# EPS_Distribution_LCL-TK.net
KiCad netlist of a schematic drawn in Altium Designer
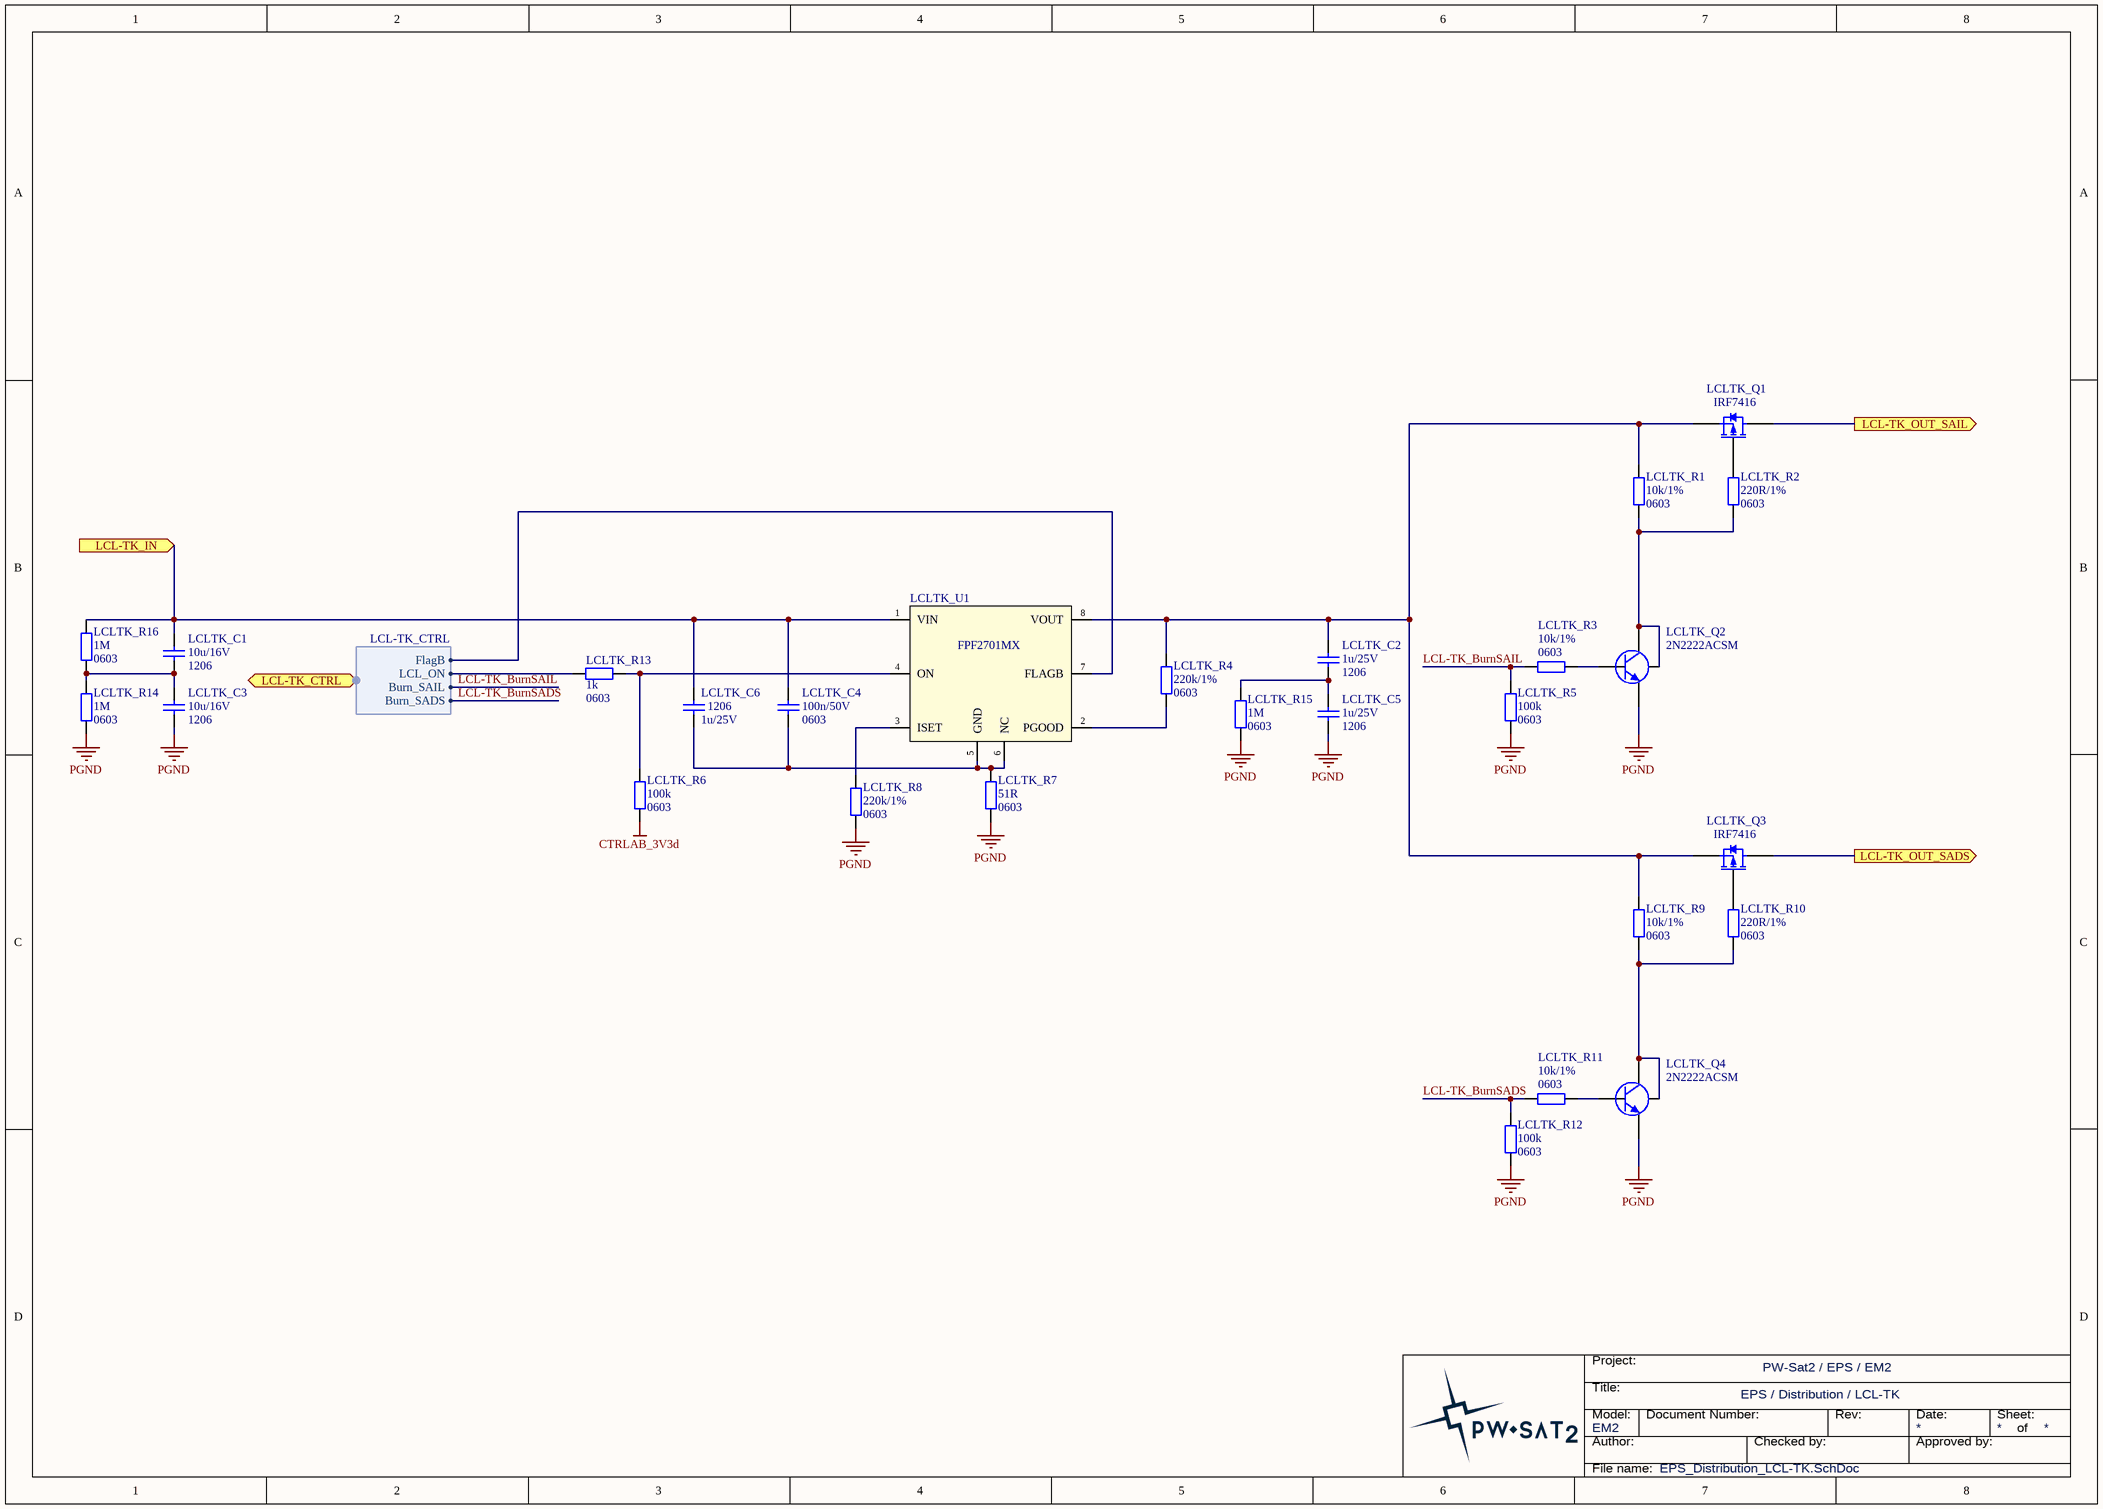
[diagram p0: EPS_Distribution_LCL-TK.SchDoc]

(export (version "E")
  (design (tool "Eeschema 10.0.6"))
  (components
    (comp (ref "LCLTK_C1")
      (value "10u/16V")
      (footprint "SMD_Capacitor_1206")
      (description "Ceramic Cap Kemet COTS 10u/16V X7R 1206")
      (fields
        (field (name "MANUFACTURERPARTNUMBER") "C1206T106K4RACTU")
        (field (name "MANUFACTURER") "Kemet")
        (field (name "PACKGE") "1206")
      )
      (libsource (lib "capacitors") (part "Cer_C1206T106K4RACTU"))
    )
    (comp (ref "LCLTK_C2")
      (value "1u/25V")
      (footprint "SMD_Capacitor_1206")
      (description "Ceramic Cap Kemet COTS 1u/25V X7R 1206")
      (fields
        (field (name "MANUFACTURERPARTNUMBER") "C1206T105K3RALTU")
        (field (name "MANUFACTURER") "Kemet")
        (field (name "PACKAGE") "1206")
      )
      (libsource (lib "capacitors") (part "Cer_C1206T105K3RALTU"))
    )
    (comp (ref "LCLTK_C3")
      (value "10u/16V")
      (footprint "SMD_Capacitor_1206")
      (description "Ceramic Cap Kemet COTS 10u/16V X7R 1206")
      (fields
        (field (name "MANUFACTURERPARTNUMBER") "C1206T106K4RACTU")
        (field (name "MANUFACTURER") "Kemet")
        (field (name "PACKGE") "1206")
      )
      (libsource (lib "capacitors") (part "Cer_C1206T106K4RACTU"))
    )
    (comp (ref "LCLTK_C4")
      (value "100n/50V")
      (footprint "SMD_Capacitor_0603")
      (description "Ceramic Cap Kemet COTS 100n/50V X7R 0603")
      (fields
        (field (name "MANUFACTURER") "Kemet")
        (field (name "MANUFACTURERPARTNUMBER") "C0603T104K5RALTU")
        (field (name "PACKAGE") "0603")
      )
      (libsource (lib "capacitors") (part "Cer_C0603T104K5RALTU"))
    )
    (comp (ref "LCLTK_C5")
      (value "1u/25V")
      (footprint "SMD_Capacitor_1206")
      (description "Ceramic Cap Kemet COTS 1u/25V X7R 1206")
      (fields
        (field (name "MANUFACTURERPARTNUMBER") "C1206T105K3RALTU")
        (field (name "MANUFACTURER") "Kemet")
        (field (name "PACKAGE") "1206")
      )
      (libsource (lib "capacitors") (part "Cer_C1206T105K3RALTU"))
    )
    (comp (ref "LCLTK_C6")
      (value "1u/25V")
      (footprint "SMD_Capacitor_1206")
      (description "Ceramic Cap Kemet COTS 1u/25V X7R 1206")
      (fields
        (field (name "MANUFACTURERPARTNUMBER") "C1206T105K3RALTU")
        (field (name "MANUFACTURER") "Kemet")
        (field (name "PACKAGE") "1206")
      )
      (libsource (lib "capacitors") (part "Cer_C1206T105K3RALTU"))
    )
    (comp (ref "LCLTK_Q1")
      (value "IRF7416")
      (footprint "SOIC-8-N_SSSGDDDD")
      (description "10A/30V HEXFET Power P-MOSFET.")
      (fields (field (name "MANUFACTURER") "International Rectifier"))
      (libsource (lib "transistors") (part "IRF7416"))
    )
    (comp (ref "LCLTK_Q2")
      (value "2N2222ACSM")
      (footprint "LCC1-4_BEC")
      (description "Silicon Planar Epitaxial NPN Transistor.")
      (fields (field (name "MANUFACTURER") "Semelab-TT"))
      (libsource (lib "transistors") (part "2N2222ACSM"))
    )
    (comp (ref "LCLTK_Q3")
      (value "IRF7416")
      (footprint "SOIC-8-N_SSSGDDDD")
      (description "10A/30V HEXFET Power P-MOSFET.")
      (fields (field (name "MANUFACTURER") "International Rectifier"))
      (libsource (lib "transistors") (part "IRF7416"))
    )
    (comp (ref "LCLTK_Q4")
      (value "2N2222ACSM")
      (footprint "LCC1-4_BEC")
      (description "Silicon Planar Epitaxial NPN Transistor.")
      (fields (field (name "MANUFACTURER") "Semelab-TT"))
      (libsource (lib "transistors") (part "2N2222ACSM"))
    )
    (comp (ref "LCLTK_R1")
      (value "10k/1%")
      (footprint "SMD_Resistor_0603")
      (fields (field (name "PACKAGE") "0603"))
      (libsource (lib "resistors") (part "Res"))
    )
    (comp (ref "LCLTK_R2")
      (value "220R/1%")
      (footprint "SMD_Resistor_0603")
      (fields (field (name "PACKAGE") "0603"))
      (libsource (lib "resistors") (part "Res"))
    )
    (comp (ref "LCLTK_R3")
      (value "10k/1%")
      (footprint "SMD_Resistor_0603")
      (fields (field (name "PACKAGE") "0603"))
      (libsource (lib "") (part "Res_1"))
    )
    (comp (ref "LCLTK_R4")
      (value "220k/1%")
      (footprint "SMD_Resistor_0603")
      (fields (field (name "PACKAGE") "0603"))
      (libsource (lib "resistors") (part "Res"))
    )
    (comp (ref "LCLTK_R5")
      (value "100k")
      (footprint "SMD_Resistor_0603")
      (fields (field (name "PACKAGE") "0603"))
      (libsource (lib "resistors") (part "Res"))
    )
    (comp (ref "LCLTK_R6")
      (value "100k")
      (footprint "SMD_Resistor_0603")
      (fields (field (name "PACKAGE") "0603"))
      (libsource (lib "resistors") (part "Res"))
    )
    (comp (ref "LCLTK_R7")
      (value "51R")
      (footprint "SMD_Resistor_0603")
      (fields (field (name "PACKAGE") "0603"))
      (libsource (lib "resistors") (part "Res"))
    )
    (comp (ref "LCLTK_R8")
      (value "220k/1%")
      (footprint "SMD_Resistor_0603")
      (fields (field (name "PACKAGE") "0603"))
      (libsource (lib "resistors") (part "Res"))
    )
    (comp (ref "LCLTK_R9")
      (value "10k/1%")
      (footprint "SMD_Resistor_0603")
      (fields (field (name "PACKAGE") "0603"))
      (libsource (lib "resistors") (part "Res"))
    )
    (comp (ref "LCLTK_R10")
      (value "220R/1%")
      (footprint "SMD_Resistor_0603")
      (fields (field (name "PACKAGE") "0603"))
      (libsource (lib "resistors") (part "Res"))
    )
    (comp (ref "LCLTK_R11")
      (value "10k/1%")
      (footprint "SMD_Resistor_0603")
      (fields (field (name "PACKAGE") "0603"))
      (libsource (lib "") (part "Res_1"))
    )
    (comp (ref "LCLTK_R12")
      (value "100k")
      (footprint "SMD_Resistor_0603")
      (fields (field (name "PACKAGE") "0603"))
      (libsource (lib "resistors") (part "Res"))
    )
    (comp (ref "LCLTK_R13")
      (value "1k")
      (footprint "SMD_Resistor_0603")
      (fields (field (name "PACKAGE") "0603"))
      (libsource (lib "") (part "Res_1"))
    )
    (comp (ref "LCLTK_R14")
      (value "1M")
      (footprint "SMD_Resistor_0603")
      (fields (field (name "PACKAGE") "0603"))
      (libsource (lib "resistors") (part "Res"))
    )
    (comp (ref "LCLTK_R15")
      (value "1M")
      (footprint "SMD_Resistor_0603")
      (fields (field (name "PACKAGE") "0603"))
      (libsource (lib "resistors") (part "Res"))
    )
    (comp (ref "LCLTK_R16")
      (value "1M")
      (footprint "SMD_Resistor_0603")
      (fields (field (name "PACKAGE") "0603"))
      (libsource (lib "resistors") (part "Res"))
    )
    (comp (ref "LCLTK_U1")
      (value "FPF2701MX")
      (footprint "SOIC-8-N")
      (description "Adj over-current protection 0.4-2A, Load Switch")
      (fields (field (name "MANUFACTURER") "Fairchild Semiconductor"))
      (libsource (lib "microcircuits") (part "FPF2701MX"))
    )
  )
  (nets
    (net (code "2") (name "/FlagB") (class "Default")
      (node (ref "LCLTK_U1") (pin "7") (pinfunction "FLAGB_7") (pintype "passive"))
    )
    (net (code "3") (name "/LCL-TK_BurnSADS") (class "Default")
      (node (ref "LCLTK_R11") (pin "2") (pinfunction "2_2") (pintype "passive"))
      (node (ref "LCLTK_R12") (pin "2") (pinfunction "2_2") (pintype "passive"))
    )
    (net (code "4") (name "/LCL-TK_BurnSAIL") (class "Default")
      (node (ref "LCLTK_R3") (pin "2") (pinfunction "2_2") (pintype "passive"))
      (node (ref "LCLTK_R5") (pin "2") (pinfunction "2_2") (pintype "passive"))
    )
    (net (code "5") (name "/LCL-TK_IN") (class "Default")
      (node (ref "LCLTK_C1") (pin "1") (pinfunction "1_1") (pintype "passive"))
      (node (ref "LCLTK_C4") (pin "1") (pinfunction "1_1") (pintype "passive"))
      (node (ref "LCLTK_C6") (pin "1") (pinfunction "1_1") (pintype "passive"))
      (node (ref "LCLTK_R16") (pin "2") (pinfunction "2_2") (pintype "passive"))
      (node (ref "LCLTK_U1") (pin "1") (pinfunction "VIN_1") (pintype "passive"))
    )
    (net (code "6") (name "/LCL-TK_OUT_SADS") (class "Default")
      (node (ref "LCLTK_Q3") (pin "D") (pinfunction "D_D") (pintype "passive"))
    )
    (net (code "7") (name "/LCL-TK_OUT_SAIL") (class "Default")
      (node (ref "LCLTK_Q1") (pin "D") (pinfunction "D_D") (pintype "passive"))
    )
    (net (code "8") (name "/LCL_ON") (class "Default")
      (node (ref "LCLTK_R13") (pin "2") (pinfunction "2_2") (pintype "passive"))
    )
    (net (code "10") (name "CTRLAB_3V3d") (class "Default")
      (node (ref "LCLTK_R6") (pin "1") (pinfunction "1_1") (pintype "passive"))
    )
    (net (code "11") (name "Net-(LCLTK_C1-Pad2)") (class "Default")
      (node (ref "LCLTK_C1") (pin "2") (pinfunction "2_2") (pintype "passive"))
      (node (ref "LCLTK_C3") (pin "1") (pinfunction "1_1") (pintype "passive"))
      (node (ref "LCLTK_R14") (pin "2") (pinfunction "2_2") (pintype "passive"))
      (node (ref "LCLTK_R16") (pin "1") (pinfunction "1_1") (pintype "passive"))
    )
    (net (code "12") (name "Net-(LCLTK_C2-Pad2)") (class "Default")
      (node (ref "LCLTK_C2") (pin "2") (pinfunction "2_2") (pintype "passive"))
      (node (ref "LCLTK_C5") (pin "1") (pinfunction "1_1") (pintype "passive"))
      (node (ref "LCLTK_R15") (pin "2") (pinfunction "2_2") (pintype "passive"))
    )
    (net (code "13") (name "Net-(LCLTK_Q1-PadG)") (class "Default")
      (node (ref "LCLTK_Q1") (pin "G") (pinfunction "G_G") (pintype "passive"))
      (node (ref "LCLTK_R2") (pin "2") (pinfunction "2_2") (pintype "passive"))
    )
    (net (code "14") (name "Net-(LCLTK_Q2-PadB)") (class "Default")
      (node (ref "LCLTK_Q2") (pin "B") (pinfunction "B_B") (pintype "passive"))
      (node (ref "LCLTK_R3") (pin "1") (pinfunction "1_1") (pintype "passive"))
    )
    (net (code "15") (name "Net-(LCLTK_Q2-PadC)") (class "Default")
      (node (ref "LCLTK_Q2") (pin "C") (pinfunction "C_C") (pintype "passive"))
      (node (ref "LCLTK_Q2") (pin "Shield") (pinfunction "Shield_Shield") (pintype "passive"))
      (node (ref "LCLTK_R1") (pin "1") (pinfunction "1_1") (pintype "passive"))
      (node (ref "LCLTK_R2") (pin "1") (pinfunction "1_1") (pintype "passive"))
    )
    (net (code "16") (name "Net-(LCLTK_Q3-PadG)") (class "Default")
      (node (ref "LCLTK_Q3") (pin "G") (pinfunction "G_G") (pintype "passive"))
      (node (ref "LCLTK_R10") (pin "2") (pinfunction "2_2") (pintype "passive"))
    )
    (net (code "17") (name "Net-(LCLTK_Q4-PadB)") (class "Default")
      (node (ref "LCLTK_Q4") (pin "B") (pinfunction "B_B") (pintype "passive"))
      (node (ref "LCLTK_R11") (pin "1") (pinfunction "1_1") (pintype "passive"))
    )
    (net (code "18") (name "Net-(LCLTK_Q4-PadC)") (class "Default")
      (node (ref "LCLTK_Q4") (pin "C") (pinfunction "C_C") (pintype "passive"))
      (node (ref "LCLTK_Q4") (pin "Shield") (pinfunction "Shield_Shield") (pintype "passive"))
      (node (ref "LCLTK_R10") (pin "1") (pinfunction "1_1") (pintype "passive"))
      (node (ref "LCLTK_R9") (pin "1") (pinfunction "1_1") (pintype "passive"))
    )
    (net (code "19") (name "Net-(LCLTK_U1-GND)") (class "Default")
      (node (ref "LCLTK_C4") (pin "2") (pinfunction "2_2") (pintype "passive"))
      (node (ref "LCLTK_C6") (pin "2") (pinfunction "2_2") (pintype "passive"))
      (node (ref "LCLTK_R7") (pin "2") (pinfunction "2_2") (pintype "passive"))
      (node (ref "LCLTK_U1") (pin "5") (pinfunction "GND_5") (pintype "passive"))
      (node (ref "LCLTK_U1") (pin "6") (pinfunction "NC_6") (pintype "passive"))
    )
    (net (code "20") (name "Net-(LCLTK_U1-ISET)") (class "Default")
      (node (ref "LCLTK_R8") (pin "2") (pinfunction "2_2") (pintype "passive"))
      (node (ref "LCLTK_U1") (pin "3") (pinfunction "ISET_3") (pintype "passive"))
    )
    (net (code "21") (name "Net-(LCLTK_U1-ON)") (class "Default")
      (node (ref "LCLTK_R13") (pin "1") (pinfunction "1_1") (pintype "passive"))
      (node (ref "LCLTK_R6") (pin "2") (pinfunction "2_2") (pintype "passive"))
      (node (ref "LCLTK_U1") (pin "4") (pinfunction "ON_4") (pintype "passive"))
    )
    (net (code "22") (name "Net-(LCLTK_U1-PGOOD)") (class "Default")
      (node (ref "LCLTK_R4") (pin "1") (pinfunction "1_1") (pintype "passive"))
      (node (ref "LCLTK_U1") (pin "2") (pinfunction "PGOOD_2") (pintype "passive"))
    )
    (net (code "23") (name "Net-(LCLTK_U1-VOUT)") (class "Default")
      (node (ref "LCLTK_C2") (pin "1") (pinfunction "1_1") (pintype "passive"))
      (node (ref "LCLTK_Q1") (pin "S") (pinfunction "S_S") (pintype "passive"))
      (node (ref "LCLTK_Q3") (pin "S") (pinfunction "S_S") (pintype "passive"))
      (node (ref "LCLTK_R1") (pin "2") (pinfunction "2_2") (pintype "passive"))
      (node (ref "LCLTK_R4") (pin "2") (pinfunction "2_2") (pintype "passive"))
      (node (ref "LCLTK_R9") (pin "2") (pinfunction "2_2") (pintype "passive"))
      (node (ref "LCLTK_U1") (pin "8") (pinfunction "VOUT_8") (pintype "passive"))
    )
    (net (code "24") (name "PGND") (class "Default")
      (node (ref "LCLTK_C3") (pin "2") (pinfunction "2_2") (pintype "passive"))
      (node (ref "LCLTK_C5") (pin "2") (pinfunction "2_2") (pintype "passive"))
      (node (ref "LCLTK_Q2") (pin "E") (pinfunction "E_E") (pintype "passive"))
      (node (ref "LCLTK_Q4") (pin "E") (pinfunction "E_E") (pintype "passive"))
      (node (ref "LCLTK_R12") (pin "1") (pinfunction "1_1") (pintype "passive"))
      (node (ref "LCLTK_R14") (pin "1") (pinfunction "1_1") (pintype "passive"))
      (node (ref "LCLTK_R15") (pin "1") (pinfunction "1_1") (pintype "passive"))
      (node (ref "LCLTK_R5") (pin "1") (pinfunction "1_1") (pintype "passive"))
      (node (ref "LCLTK_R7") (pin "1") (pinfunction "1_1") (pintype "passive"))
      (node (ref "LCLTK_R8") (pin "1") (pinfunction "1_1") (pintype "passive"))
    )
  )
)
